# Peripherals_connectors.net
KiCad netlist of a schematic drawn in Altium Designer
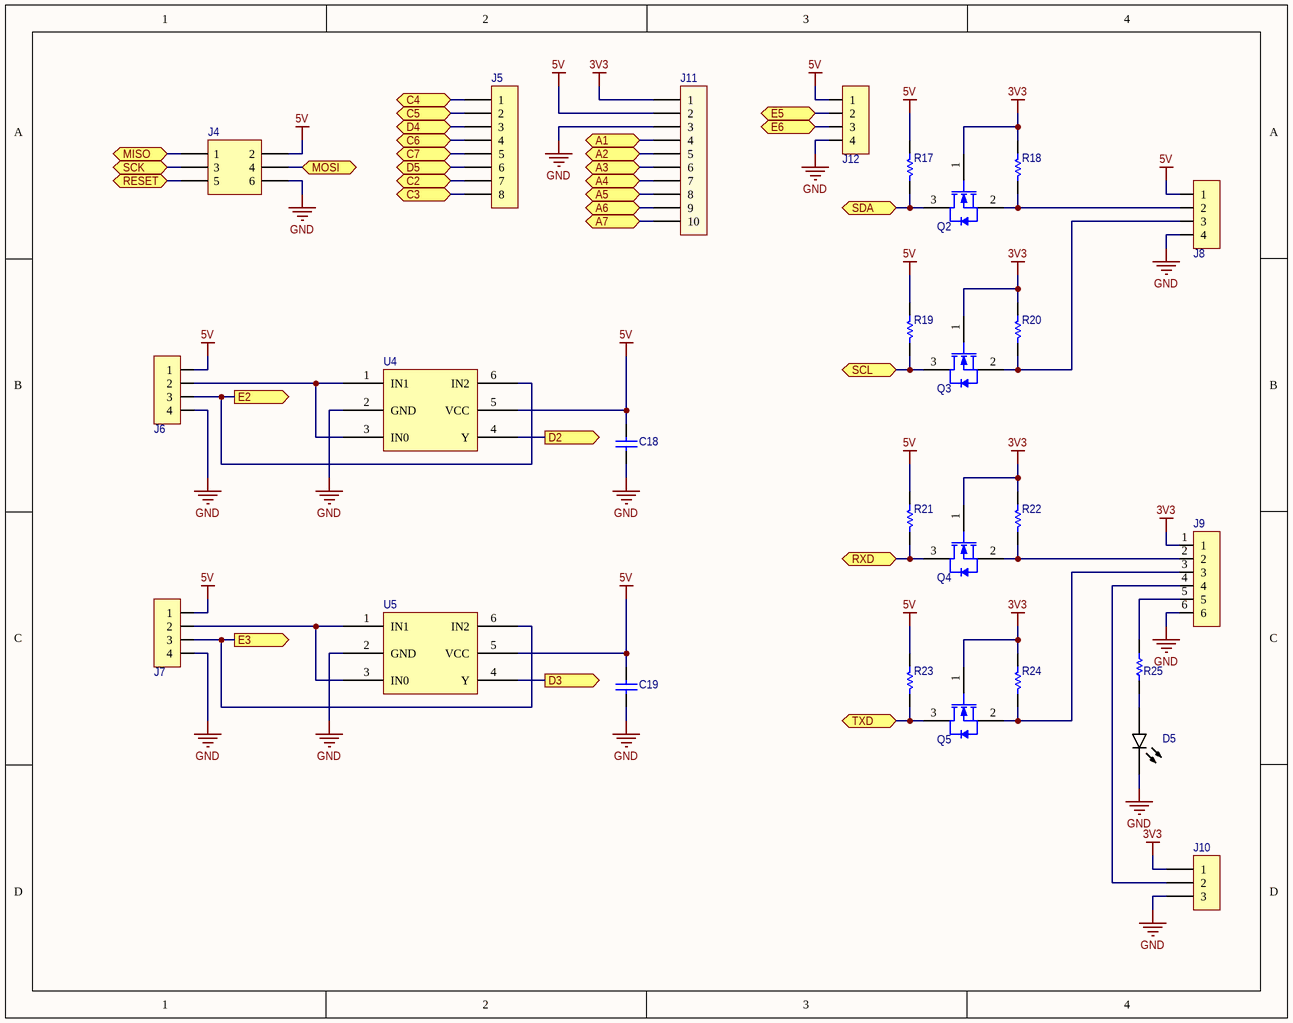
[diagram p0: Peripherals connectors.SchDoc]

(export (version "E")
  (design (tool "Eeschema 10.0.6"))
  (components
    (comp (ref "C18")
      (value "Kemet C1206C104K5RACAUTO")
      (footprint "CAPC3216X88X50ML20T25")
      (description "Cap Ceramic 0.1uF 50V X7R 10% SMD 1206 125C Plastic T/R")
      (fields (field (name "MANUFACTURER PART NUMBER") "C1206C104K5RACAUTO"))
      (libsource (lib "Octopart library") (part "CAP-2"))
    )
    (comp (ref "C19")
      (value "Kemet C1206C104K5RACAUTO")
      (footprint "CAPC3216X88X50ML20T25")
      (description "Cap Ceramic 0.1uF 50V X7R 10% SMD 1206 125C Plastic T/R")
      (fields (field (name "MANUFACTURER PART NUMBER") "C1206C104K5RACAUTO"))
      (libsource (lib "Octopart library") (part "CAP-2"))
    )
    (comp (ref "D5")
      (value "Lite-On LTST-C170TBKT")
      (footprint "CHIPLED  0805 BLUE")
      (description "Blue 2 x 1.25 x 1.1 mm 130° Water Clear 112 mcd 3.8 V LED Surface Mount")
      (libsource (lib "Octopart library") (part "SYM-173fdfefd1b8c8f8-1"))
    )
    (comp (ref "J4")
      (value "FCI 67996-206HLF")
      (footprint "PCB-av458rj4t6vupn2hcvqe-1")
      (description "Conn Unshrouded Header HDR 6 POS 2.54mm Solder ST Thru-Hole Poly Bag")
      (fields (field (name "MANUFACTURER PART NUMBER") "67996-206HLF"))
      (libsource (lib "CommunityVault") (part "SYM-bc8877e797ed634f-1"))
    )
    (comp (ref "J5")
      (value "Samtec MMS-108-01-L-SV")
      (footprint "PCB-goc1bdntoqdy8u4hrzei-1")
      (description "Conn Socket Strip SKT 8 POS 2mm Solder ST Thru-Hole Tube")
      (fields (field (name "MANUFACTURER PART NUMBER") "MMS-108-01-L-SV"))
      (libsource (lib "CommunityVault") (part "CMP-11ccd8c2bcd6ce0b-2"))
    )
    (comp (ref "J6")
      (value "4pin header")
      (footprint "PCBComponent_1 - duplicate")
      (description "Conn Unshrouded Header HDR 4 POS 2.54mm Solder ST Thru-Hole C-Grid III™ Tray")
      (fields (field (name "MANUFACTURER PART NUMBER") "0901200124"))
      (libsource (lib "CommunityVault") (part "SYM-8fae46aeaafe5069-11"))
    )
    (comp (ref "J7")
      (value "4pin header")
      (footprint "PCBComponent_1 - duplicate")
      (description "Conn Unshrouded Header HDR 4 POS 2.54mm Solder ST Thru-Hole C-Grid III™ Tray")
      (fields (field (name "MANUFACTURER PART NUMBER") "0901200124"))
      (libsource (lib "CommunityVault") (part "SYM-8fae46aeaafe5069-11"))
    )
    (comp (ref "J8")
      (value "4pin header")
      (footprint "PCBComponent_1 - duplicate")
      (description "Conn Unshrouded Header HDR 4 POS 2.54mm Solder ST Thru-Hole C-Grid III™ Tray")
      (fields (field (name "MANUFACTURER PART NUMBER") "0901200124"))
      (libsource (lib "") (part "SYM-8fae46aeaafe5069-11_1"))
    )
    (comp (ref "J9")
      (value "TE Connectivity / AMP 3-644456-5")
      (footprint "PCB-oudem42uhcimrbfznktg-1")
      (description "MTA-100 Series 6 Position 2.54 mm Pitch Single Row Tin Plated Header")
      (libsource (lib "CommunityVault") (part "SYM-7ab1b1e1ad8ca576-3"))
    )
    (comp (ref "J10")
      (value "Molex 75757-0431")
      (footprint "Molex 75757-0431")
      (description "Conn Unshrouded Header HDR 3 POS 3.5mm Solder ST Thru-Hole Tube")
      (libsource (lib "CommunityVault") (part "SYM-6ec4a6b2c126b103-1"))
    )
    (comp (ref "J11")
      (value "Jameco Valuepro 7000-1X10SG-R")
      (footprint "PCB-pv1vym0ok8u0vunn5wic-1")
      (description "Header Straight Male 1 Row 10 Pin")
      (libsource (lib "CommunityVault") (part "CMP-6671af580ca0b9b6-1"))
    )
    (comp (ref "J12")
      (value "4pin header")
      (footprint "PCBComponent_1 - duplicate")
      (description "Conn Unshrouded Header HDR 4 POS 2.54mm Solder ST Thru-Hole C-Grid III™ Tray")
      (fields (field (name "MANUFACTURER PART NUMBER") "0901200124"))
      (libsource (lib "CommunityVault") (part "CMP-6785af82bd5db842-5"))
    )
    (comp (ref "Q2")
      (value "SYM-ec4d21f6be82338a-2")
      (footprint "PCB-fnvh88uh0gwuonmuoobt-1")
      (fields (field (name "MANUFACTURER PART NUMBER") "BSS138P,215"))
      (libsource (lib "Octopart library") (part "SYM-ec4d21f6be82338a-2"))
    )
    (comp (ref "Q3")
      (value "SYM-ec4d21f6be82338a-2")
      (footprint "PCB-fnvh88uh0gwuonmuoobt-1")
      (fields (field (name "MANUFACTURER PART NUMBER") "BSS138P,215"))
      (libsource (lib "Octopart library") (part "SYM-ec4d21f6be82338a-2"))
    )
    (comp (ref "Q4")
      (value "SYM-ec4d21f6be82338a-2")
      (footprint "PCB-fnvh88uh0gwuonmuoobt-1")
      (fields (field (name "MANUFACTURER PART NUMBER") "BSS138P,215"))
      (libsource (lib "Octopart library") (part "SYM-ec4d21f6be82338a-2"))
    )
    (comp (ref "Q5")
      (value "SYM-ec4d21f6be82338a-2")
      (footprint "PCB-fnvh88uh0gwuonmuoobt-1")
      (fields (field (name "MANUFACTURER PART NUMBER") "BSS138P,215"))
      (libsource (lib "Octopart library") (part "SYM-ec4d21f6be82338a-2"))
    )
    (comp (ref "R17")
      (value "Res1")
      (footprint "PCB-r93x9swl7vzrlon1kcic-1")
      (description "Res Thick Film 1206 10K Ohm 1% 1/4W ±100ppm/°C Molded SMD SMD Paper T/R")
      (fields (field (name "MANUFACTURER PART NUMBER") "CRCW120610K0FKTA"))
      (libsource (lib "Octopart library") (part "SYM-1d37d65bd2a0c2f0-1"))
    )
    (comp (ref "R18")
      (value "Res1")
      (footprint "PCB-r93x9swl7vzrlon1kcic-1")
      (description "Res Thick Film 1206 10K Ohm 1% 1/4W ±100ppm/°C Molded SMD SMD Paper T/R")
      (fields (field (name "MANUFACTURER PART NUMBER") "CRCW120610K0FKTA"))
      (libsource (lib "Octopart library") (part "SYM-1d37d65bd2a0c2f0-1"))
    )
    (comp (ref "R19")
      (value "Res1")
      (footprint "PCB-r93x9swl7vzrlon1kcic-1")
      (description "Res Thick Film 1206 10K Ohm 1% 1/4W ±100ppm/°C Molded SMD SMD Paper T/R")
      (fields (field (name "MANUFACTURER PART NUMBER") "CRCW120610K0FKTA"))
      (libsource (lib "Octopart library") (part "SYM-1d37d65bd2a0c2f0-1"))
    )
    (comp (ref "R20")
      (value "Res1")
      (footprint "PCB-r93x9swl7vzrlon1kcic-1")
      (description "Res Thick Film 1206 10K Ohm 1% 1/4W ±100ppm/°C Molded SMD SMD Paper T/R")
      (fields (field (name "MANUFACTURER PART NUMBER") "CRCW120610K0FKTA"))
      (libsource (lib "CommunityVault") (part "SYM-1d37d65bd2a0c2f0-1"))
    )
    (comp (ref "R21")
      (value "Res1")
      (footprint "PCB-r93x9swl7vzrlon1kcic-1")
      (description "Res Thick Film 1206 10K Ohm 1% 1/4W ±100ppm/°C Molded SMD SMD Paper T/R")
      (fields (field (name "MANUFACTURER PART NUMBER") "CRCW120610K0FKTA"))
      (libsource (lib "Octopart library") (part "SYM-1d37d65bd2a0c2f0-1"))
    )
    (comp (ref "R22")
      (value "Res1")
      (footprint "PCB-r93x9swl7vzrlon1kcic-1")
      (description "Res Thick Film 1206 10K Ohm 1% 1/4W ±100ppm/°C Molded SMD SMD Paper T/R")
      (fields (field (name "MANUFACTURER PART NUMBER") "CRCW120610K0FKTA"))
      (libsource (lib "Octopart library") (part "SYM-1d37d65bd2a0c2f0-1"))
    )
    (comp (ref "R23")
      (value "Res1")
      (footprint "PCB-r93x9swl7vzrlon1kcic-1")
      (description "Res Thick Film 1206 10K Ohm 1% 1/4W ±100ppm/°C Molded SMD SMD Paper T/R")
      (fields (field (name "MANUFACTURER PART NUMBER") "CRCW120610K0FKTA"))
      (libsource (lib "Octopart library") (part "SYM-1d37d65bd2a0c2f0-1"))
    )
    (comp (ref "R24")
      (value "Res1")
      (footprint "PCB-r93x9swl7vzrlon1kcic-1")
      (description "Res Thick Film 1206 10K Ohm 1% 1/4W ±100ppm/°C Molded SMD SMD Paper T/R")
      (fields (field (name "MANUFACTURER PART NUMBER") "CRCW120610K0FKTA"))
      (libsource (lib "Octopart library") (part "SYM-1d37d65bd2a0c2f0-1"))
    )
    (comp (ref "R25")
      (value "Vishay Dale CRCW12061K00FKEB")
      (footprint "RESC3216X60X45ML10T20")
      (description "Thick Film Resistors - SMD 1/4watt 1Kohms 1%")
      (fields (field (name "MANUFACTURER PART NUMBER") "CRCW12061K00FKEB"))
      (libsource (lib "Octopart library") (part "RES-2"))
    )
    (comp (ref "U4")
      (value "Diodes Inc. 74LVC1G58W6-7")
      (footprint "PCB-s3ckst0z292py2klz87t-1")
      (description "LOGIC, POS MULTI FUNC, 3 IP, SOT26; Logic Type: Configurable Multiple Function; O")
      (libsource (lib "Octopart library") (part "SYM-b0da78e2508a6f1d-1"))
    )
    (comp (ref "U5")
      (value "Diodes Inc. 74LVC1G58W6-7")
      (footprint "PCB-s3ckst0z292py2klz87t-1")
      (description "LOGIC, POS MULTI FUNC, 3 IP, SOT26; Logic Type: Configurable Multiple Function; O")
      (libsource (lib "Octopart library") (part "SYM-b0da78e2508a6f1d-1"))
    )
  )
  (nets
    (net (code "1") (name "/A1") (class "Default")
      (node (ref "J11") (pin "4") (pinfunction "4_4") (pintype "passive"))
    )
    (net (code "2") (name "/A2") (class "Default")
      (node (ref "J11") (pin "5") (pinfunction "5_5") (pintype "passive"))
    )
    (net (code "3") (name "/A3") (class "Default")
      (node (ref "J11") (pin "6") (pinfunction "6_6") (pintype "passive"))
    )
    (net (code "4") (name "/A4") (class "Default")
      (node (ref "J11") (pin "7") (pinfunction "7_7") (pintype "passive"))
    )
    (net (code "5") (name "/A5") (class "Default")
      (node (ref "J11") (pin "8") (pinfunction "8_8") (pintype "passive"))
    )
    (net (code "6") (name "/A6") (class "Default")
      (node (ref "J11") (pin "9") (pinfunction "9_9") (pintype "passive"))
    )
    (net (code "7") (name "/A7") (class "Default")
      (node (ref "J11") (pin "10") (pinfunction "10_10") (pintype "passive"))
    )
    (net (code "8") (name "/C2") (class "Default")
      (node (ref "J5") (pin "7") (pinfunction "7_7") (pintype "passive"))
    )
    (net (code "9") (name "/C3") (class "Default")
      (node (ref "J5") (pin "8") (pinfunction "8_8") (pintype "passive"))
    )
    (net (code "10") (name "/C4") (class "Default")
      (node (ref "J5") (pin "1") (pinfunction "1_1") (pintype "passive"))
    )
    (net (code "11") (name "/C5") (class "Default")
      (node (ref "J5") (pin "2") (pinfunction "2_2") (pintype "passive"))
    )
    (net (code "12") (name "/C6") (class "Default")
      (node (ref "J5") (pin "4") (pinfunction "4_4") (pintype "passive"))
    )
    (net (code "13") (name "/C7") (class "Default")
      (node (ref "J5") (pin "5") (pinfunction "5_5") (pintype "passive"))
    )
    (net (code "14") (name "/D2") (class "Default")
      (node (ref "U4") (pin "4") (pinfunction "Y_4") (pintype "passive"))
    )
    (net (code "15") (name "/D3") (class "Default")
      (node (ref "U5") (pin "4") (pinfunction "Y_4") (pintype "passive"))
    )
    (net (code "16") (name "/D4") (class "Default")
      (node (ref "J5") (pin "3") (pinfunction "3_3") (pintype "passive"))
    )
    (net (code "17") (name "/D5") (class "Default")
      (node (ref "J5") (pin "6") (pinfunction "6_6") (pintype "passive"))
    )
    (net (code "18") (name "/E2") (class "Default")
      (node (ref "J6") (pin "3") (pinfunction "3_3") (pintype "passive"))
      (node (ref "U4") (pin "6") (pinfunction "IN2_6") (pintype "passive"))
    )
    (net (code "19") (name "/E3") (class "Default")
      (node (ref "J7") (pin "3") (pinfunction "3_3") (pintype "passive"))
      (node (ref "U5") (pin "6") (pinfunction "IN2_6") (pintype "passive"))
    )
    (net (code "20") (name "/E5") (class "Default")
      (node (ref "J12") (pin "2") (pinfunction "2_2") (pintype "passive"))
    )
    (net (code "21") (name "/E6") (class "Default")
      (node (ref "J12") (pin "3") (pinfunction "3_3") (pintype "passive"))
    )
    (net (code "22") (name "/MISO") (class "Default")
      (node (ref "J4") (pin "1") (pinfunction "1_1") (pintype "passive"))
    )
    (net (code "23") (name "/MOSI") (class "Default")
      (node (ref "J4") (pin "4") (pinfunction "4_4") (pintype "passive"))
    )
    (net (code "24") (name "/RESET") (class "Default")
      (node (ref "J4") (pin "5") (pinfunction "5_5") (pintype "passive"))
    )
    (net (code "25") (name "/RXD") (class "Default")
      (node (ref "Q4") (pin "3") (pinfunction "D_3") (pintype "passive"))
      (node (ref "R21") (pin "2") (pinfunction "2_2") (pintype "passive"))
    )
    (net (code "26") (name "/SCK") (class "Default")
      (node (ref "J4") (pin "3") (pinfunction "3_3") (pintype "passive"))
    )
    (net (code "27") (name "/SCL") (class "Default")
      (node (ref "Q3") (pin "3") (pinfunction "D_3") (pintype "passive"))
      (node (ref "R19") (pin "2") (pinfunction "2_2") (pintype "passive"))
    )
    (net (code "28") (name "/SDA") (class "Default")
      (node (ref "Q2") (pin "3") (pinfunction "D_3") (pintype "passive"))
      (node (ref "R17") (pin "2") (pinfunction "2_2") (pintype "passive"))
    )
    (net (code "29") (name "/TXD") (class "Default")
      (node (ref "Q5") (pin "3") (pinfunction "D_3") (pintype "passive"))
      (node (ref "R23") (pin "2") (pinfunction "2_2") (pintype "passive"))
    )
    (net (code "30") (name "3V3") (class "Default")
      (node (ref "J10") (pin "1") (pinfunction "1_1") (pintype "passive"))
      (node (ref "J11") (pin "1") (pinfunction "1_1") (pintype "passive"))
      (node (ref "J9") (pin "1") (pinfunction "1_1") (pintype "passive"))
      (node (ref "Q2") (pin "1") (pinfunction "G_1") (pintype "passive"))
      (node (ref "Q3") (pin "1") (pinfunction "G_1") (pintype "passive"))
      (node (ref "Q4") (pin "1") (pinfunction "G_1") (pintype "passive"))
      (node (ref "Q5") (pin "1") (pinfunction "G_1") (pintype "passive"))
      (node (ref "R18") (pin "1") (pinfunction "1_1") (pintype "passive"))
      (node (ref "R20") (pin "1") (pinfunction "1_1") (pintype "passive"))
      (node (ref "R22") (pin "1") (pinfunction "1_1") (pintype "passive"))
      (node (ref "R24") (pin "1") (pinfunction "1_1") (pintype "passive"))
    )
    (net (code "31") (name "5V") (class "Default")
      (node (ref "C18") (pin "1") (pinfunction "1_1") (pintype "passive"))
      (node (ref "C19") (pin "1") (pinfunction "1_1") (pintype "passive"))
      (node (ref "J11") (pin "2") (pinfunction "2_2") (pintype "passive"))
      (node (ref "J12") (pin "1") (pinfunction "1_1") (pintype "passive"))
      (node (ref "J4") (pin "2") (pinfunction "2_2") (pintype "passive"))
      (node (ref "J6") (pin "1") (pinfunction "1_1") (pintype "passive"))
      (node (ref "J7") (pin "1") (pinfunction "1_1") (pintype "passive"))
      (node (ref "J8") (pin "1") (pinfunction "1_1") (pintype "passive"))
      (node (ref "R17") (pin "1") (pinfunction "1_1") (pintype "passive"))
      (node (ref "R19") (pin "1") (pinfunction "1_1") (pintype "passive"))
      (node (ref "R21") (pin "1") (pinfunction "1_1") (pintype "passive"))
      (node (ref "R23") (pin "1") (pinfunction "1_1") (pintype "passive"))
      (node (ref "U4") (pin "5") (pinfunction "VCC_5") (pintype "passive"))
      (node (ref "U5") (pin "5") (pinfunction "VCC_5") (pintype "passive"))
    )
    (net (code "32") (name "GND") (class "Default")
      (node (ref "C18") (pin "2") (pinfunction "2_2") (pintype "passive"))
      (node (ref "C19") (pin "2") (pinfunction "2_2") (pintype "passive"))
      (node (ref "D5") (pin "2") (pinfunction "K_2") (pintype "passive"))
      (node (ref "J10") (pin "3") (pinfunction "3_3") (pintype "passive"))
      (node (ref "J11") (pin "3") (pinfunction "3_3") (pintype "passive"))
      (node (ref "J12") (pin "4") (pinfunction "4_4") (pintype "passive"))
      (node (ref "J4") (pin "6") (pinfunction "6_6") (pintype "passive"))
      (node (ref "J6") (pin "4") (pinfunction "4_4") (pintype "passive"))
      (node (ref "J7") (pin "4") (pinfunction "4_4") (pintype "passive"))
      (node (ref "J8") (pin "4") (pinfunction "4_4") (pintype "passive"))
      (node (ref "J9") (pin "6") (pinfunction "6_6") (pintype "passive"))
      (node (ref "U4") (pin "2") (pinfunction "GND_2") (pintype "passive"))
      (node (ref "U5") (pin "2") (pinfunction "GND_2") (pintype "passive"))
    )
    (net (code "33") (name "Net-(D5-A)") (class "Default")
      (node (ref "D5") (pin "1") (pinfunction "A_1") (pintype "passive"))
      (node (ref "R25") (pin "1") (pinfunction "1_1") (pintype "passive"))
    )
    (net (code "34") (name "Net-(J9-Pad5)") (class "Default")
      (node (ref "J9") (pin "5") (pinfunction "5_5") (pintype "passive"))
      (node (ref "R25") (pin "2") (pinfunction "2_2") (pintype "passive"))
    )
    (net (code "35") (name "Net-(J10-Pad2)") (class "Default")
      (node (ref "J10") (pin "2") (pinfunction "2_2") (pintype "passive"))
      (node (ref "J9") (pin "4") (pinfunction "4_4") (pintype "passive"))
    )
    (net (code "36") (name "Net-(Q2-S)") (class "Default")
      (node (ref "J8") (pin "2") (pinfunction "2_2") (pintype "passive"))
      (node (ref "Q2") (pin "2") (pinfunction "S_2") (pintype "passive"))
      (node (ref "R18") (pin "2") (pinfunction "2_2") (pintype "passive"))
    )
    (net (code "37") (name "Net-(Q3-S)") (class "Default")
      (node (ref "J8") (pin "3") (pinfunction "3_3") (pintype "passive"))
      (node (ref "Q3") (pin "2") (pinfunction "S_2") (pintype "passive"))
      (node (ref "R20") (pin "2") (pinfunction "2_2") (pintype "passive"))
    )
    (net (code "38") (name "Net-(Q4-S)") (class "Default")
      (node (ref "J9") (pin "2") (pinfunction "2_2") (pintype "passive"))
      (node (ref "Q4") (pin "2") (pinfunction "S_2") (pintype "passive"))
      (node (ref "R22") (pin "2") (pinfunction "2_2") (pintype "passive"))
    )
    (net (code "39") (name "Net-(Q5-S)") (class "Default")
      (node (ref "J9") (pin "3") (pinfunction "3_3") (pintype "passive"))
      (node (ref "Q5") (pin "2") (pinfunction "S_2") (pintype "passive"))
      (node (ref "R24") (pin "2") (pinfunction "2_2") (pintype "passive"))
    )
    (net (code "40") (name "Net-(U4-IN0)") (class "Default")
      (node (ref "J6") (pin "2") (pinfunction "2_2") (pintype "passive"))
      (node (ref "U4") (pin "1") (pinfunction "IN1_1") (pintype "passive"))
      (node (ref "U4") (pin "3") (pinfunction "IN0_3") (pintype "passive"))
    )
    (net (code "41") (name "Net-(U5-IN0)") (class "Default")
      (node (ref "J7") (pin "2") (pinfunction "2_2") (pintype "passive"))
      (node (ref "U5") (pin "1") (pinfunction "IN1_1") (pintype "passive"))
      (node (ref "U5") (pin "3") (pinfunction "IN0_3") (pintype "passive"))
    )
  )
)
